# 1power.net
KiCad netlist of a schematic drawn in Altium Designer
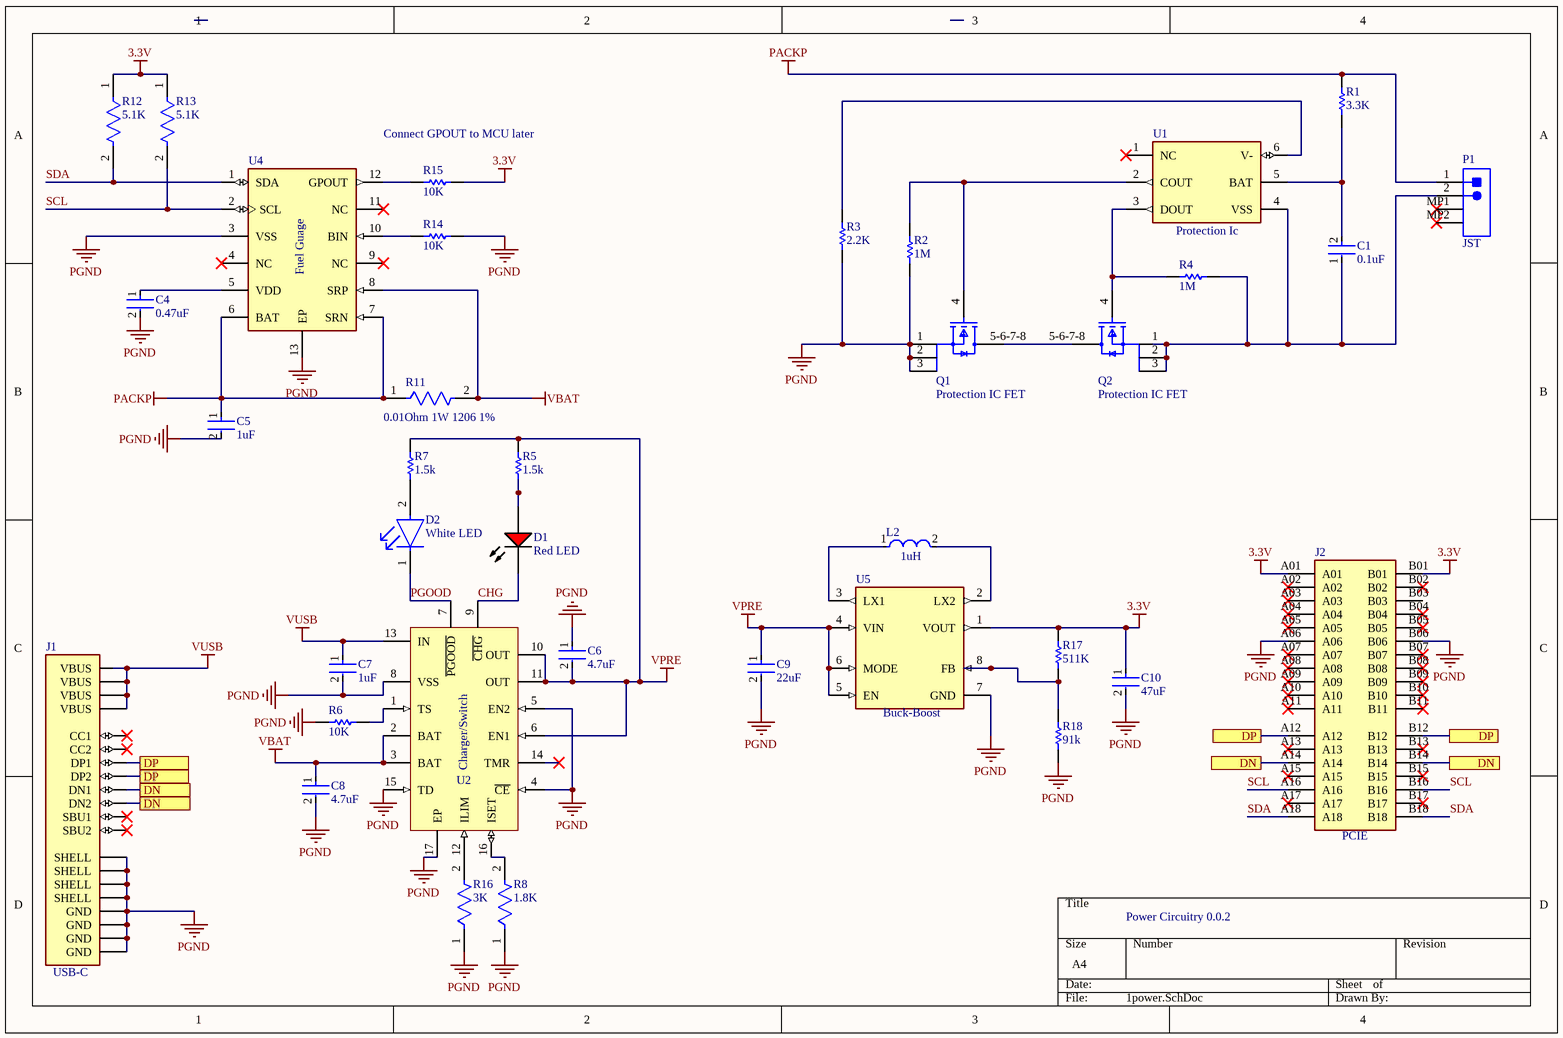
[diagram p0: 1power.SchDoc]

(export (version "E")
  (design (tool "Eeschema 10.0.6"))
  (components
    (comp (ref "C1")
      (value "0.1uF")
      (footprint "FP-GRM15-MFG")
      (description "CAP CER 0.1UF 16V X7R 0402")
      (fields (field (name "MANUFACTURER PART NUMBER") "GRM155R71C104KA88D") (field (name "TOLERANCE") "10%"))
      (libsource (lib "Altium Content Vault") (part "236180d848d6139a670b325ea6854c9"))
    )
    (comp (ref "C4")
      (value "0.47uF")
      (footprint "FP-C0603C-CF-MFG")
      (description "CAP CER 0.47UF 16V X7R 0603")
      (fields (field (name "TOLERANCE") "0.1") (field (name "MANUFACTURER PART NUMBER") "C0603C474K4RACTU"))
      (libsource (lib "Altium Content Vault") (part "b4654b650e69147ec39a6b967a45e02"))
    )
    (comp (ref "C5")
      (value "1uF")
      (footprint "FP-C0402C105K8PACTU-MFG")
      (description "CAP CER 1UF 10V X5R 0402")
      (fields (field (name "VOLTAGE") "10V") (field (name "TOLERANCE") "10%"))
      (libsource (lib "Altium Content Vault") (part "11868f565c42a9108669ba33697ecf6"))
    )
    (comp (ref "C6")
      (value "4.7uF")
      (footprint "FP-ZRB15X-0_15-MFG")
      (description "CAP CER 4.7UF 10V X5R 0402")
      (fields (field (name "TOLERANCE") "20%") (field (name "VOLTAGE") "10V"))
      (libsource (lib "Altium Content Vault") (part "b4654b650e69147ec39a6b967a45e02"))
    )
    (comp (ref "C7")
      (value "1uF")
      (footprint "FP-C0402C105K8PACTU-MFG")
      (description "CAP CER 1UF 10V X5R 0402")
      (fields (field (name "VOLTAGE") "10V") (field (name "TOLERANCE") "10%"))
      (libsource (lib "Altium Content Vault") (part "11868f565c42a9108669ba33697ecf6"))
    )
    (comp (ref "C8")
      (value "4.7uF")
      (footprint "FP-ZRB15X-0_15-MFG")
      (description "CAP CER 4.7UF 10V X5R 0402")
      (fields (field (name "TOLERANCE") "20%") (field (name "VOLTAGE") "10V"))
      (libsource (lib "Altium Content Vault") (part "b4654b650e69147ec39a6b967a45e02"))
    )
    (comp (ref "C9")
      (value "22uF")
      (footprint "FP-GRM187-0_2-IPC_C")
      (description "Chip Multilayer Ceramic Capacitors for General Purpose, 0603, 22uF, X5R, 15%, 20%, 10V")
      (fields (field (name "TOLERANCE") "20%"))
      (libsource (lib "Altium Content Vault") (part "02cd4be3c70576c341d710602a673aa"))
    )
    (comp (ref "C10")
      (value "47uF")
      (footprint "FP-GRM219-0_2-0_1-IPC_A")
      (description "Chip Multilayer Ceramic Capacitors for General Purpose, 0805, 47uF, X5R, 15%, 20%, 6.3V")
      (fields (field (name "TOLERANCE") "20%"))
      (libsource (lib "Altium Content Vault") (part "02cd4be3c70576c341d710602a673aa"))
    )
    (comp (ref "D1")
      (value "Red LED")
      (footprint "VISH-TLMS1000_V")
      (description "Low Current LED, 40 mW, 1.8 V, -40 to 100 degC, 2-Pin SMD (0603), RoHS, Tape and Reel")
      (fields (field (name "MANUFACTURER") "Vishay"))
      (libsource (lib "Altium Content Vault") (part "LED-RED-AK-2"))
    )
    (comp (ref "D2")
      (value "White LED")
      (footprint "FP-6_541-5091_01-4-MFG")
      (description "LED COOL WHITE 0603 SMD")
      (fields
        (field (name "MANUFACTURER") "Vishay")
        (field (name "MANUFACTURER PART NUMBER") "VLMW1300-GS08")
      )
      (libsource (lib "Altium Content Vault") (part "8706943c75ba83719d021d2fdc84c58"))
    )
    (comp (ref "J1")
      (value "USB-C")
      (footprint "GCT_USB4085-GF-A_REVB")
      (fields (field (name "MF") "Global Connector Technology") (field (name "MP") "USB4085-GF-A"))
      (libsource (lib "Schlib1") (part "USB4085-GF-A_REVB"))
    )
    (comp (ref "J2")
      (value "PCIE")
      (footprint "SAMTEC_PCIE-036-02-X-D-EMS3")
      (description "PCI EXPRESS EDGE MOUNT ASSEMBLY,36PINS.")
      (fields (field (name "MP") "PCIE-036-02-X-D-EMS3"))
      (libsource (lib "Schlib1") (part "PCIE-036-02-X-D-EMS3"))
    )
    (comp (ref "L2")
      (value "1uH")
      (footprint "FP-DFE252012C-IPC_B")
      (description "Shielded Wirewound Inductor 1uH 20% 3200mA 0.042Ω 1008 (2520), DFE252012P-1R0M=P2")
      (fields (field (name "TOLERANCE") "20%"))
      (libsource (lib "Altium Content Vault") (part "725321dda6339637d4d059423bc1c3c"))
    )
    (comp (ref "P1")
      (value "JST")
      (footprint "JST- S2B-PH-SM4-TB(LF)(SN)-2_V")
      (description "Male Header, Pitch 2 mm, 1 x 2 Position, Height 5.5 mm, -25 to 85 degC, RoHS, Tape and Reel")
      (libsource (lib "Schlib1") (part "CMP-1755-00001-1"))
    )
    (comp (ref "Q1")
      (value "Protection IC FET")
      (footprint "FP-DQG0008A-MFG")
      (description "Protection IC FET, MOSFET N-CH 25V 60A 8-SON, CSD16406Q3")
      (libsource (lib "Schlib1") (part "CMP-04962-000044-1"))
    )
    (comp (ref "Q2")
      (value "Protection IC FET")
      (footprint "FP-DQG0008A-MFG")
      (description "Protection IC FET, MOSFET N-CH 25V 60A 8-SON, CSD16406Q3")
      (libsource (lib "Schlib1") (part "CMP-04962-000044-1"))
    )
    (comp (ref "R1")
      (value "3.3K")
      (footprint "RESC1005X40X25LL05T10")
      (fields (field (name "MANUFACTURER") "Yageo / Phycomp") (field (name "PART NUMBER") "RC0402FR-073K3L"))
      (libsource (lib "Altium Content Vault") (part "RES"))
    )
    (comp (ref "R2")
      (value "1M")
      (footprint "RESC1005X40X25NL05T10")
      (fields (field (name "MANUFACTURER") "Yageo / Phycomp") (field (name "PART NUMBER") "RC0402FR-071ML"))
      (libsource (lib "Altium Content Vault") (part "RES"))
    )
    (comp (ref "R3")
      (value "2.2K")
      (footprint "RESC1005X40X25NL05T10")
      (fields (field (name "MANUFACTURER") "Yageo / Phycomp") (field (name "PART NUMBER") "RC0402FR-072K2L"))
      (libsource (lib "Altium Content Vault") (part "RES"))
    )
    (comp (ref "R4")
      (value "1M")
      (footprint "RESC1005X40X25NL05T10")
      (fields (field (name "MANUFACTURER") "Yageo / Phycomp") (field (name "PART NUMBER") "RC0402FR-071ML"))
      (libsource (lib "Altium Content Vault") (part "RES"))
    )
    (comp (ref "R5")
      (value "1.5k")
      (footprint "RESC1005X40X25ML05T10")
      (fields (field (name "MANUFACTURER") "Yageo / Phycomp") (field (name "PART NUMBER") "RC0402FR-071K5L"))
      (libsource (lib "Altium Content Vault") (part "RES"))
    )
    (comp (ref "R6")
      (value "10K")
      (footprint "RESC1005X40X25LL05T10")
      (fields (field (name "PART NUMBER") "RC0402FR-0710KL") (field (name "MANUFACTURER") "Yageo / Phycomp"))
      (libsource (lib "Altium Content Vault") (part "RES"))
    )
    (comp (ref "R7")
      (value "1.5k")
      (footprint "RESC1005X40X25ML05T10")
      (fields (field (name "MANUFACTURER") "Yageo / Phycomp") (field (name "PART NUMBER") "RC0402FR-071K5L"))
      (libsource (lib "Altium Content Vault") (part "RES"))
    )
    (comp (ref "R8")
      (value "1.8K")
      (footprint "FP-CRCW0603-e3-IPC_A")
      (description "RES Thick Film, 1.8kΩ, 1%, 0.1W, 100ppm/°C, 0603")
      (fields (field (name "TOLERANCE") "1%"))
      (libsource (lib "Altium Content Vault") (part "1029c3af85768c4190bb7ad29bc67b5"))
    )
    (comp (ref "R11")
      (value "0.01Ohm 1W 1206 1%")
      (footprint "FP-WSLP1206-FP_1_65x1_93x-MFG")
      (description "RES 0.01 OHM 1% 1W 1206")
      (fields (field (name "TOLERANCE") "1%"))
      (libsource (lib "Altium Content Vault") (part "1029c3af85768c4190bb7ad29bc67b5"))
    )
    (comp (ref "R12")
      (value "5.1K")
      (footprint "FP-CRCW0402-e3-IPC_A")
      (description "RES Thick Film, 5.1kΩ, 1%, 0.063W, 100ppm/°C, 0402")
      (fields (field (name "TOLERANCE") "1%"))
      (libsource (lib "Altium Content Vault") (part "1029c3af85768c4190bb7ad29bc67b5"))
    )
    (comp (ref "R13")
      (value "5.1K")
      (footprint "FP-CRCW0402-e3-IPC_A")
      (description "RES Thick Film, 5.1kΩ, 1%, 0.063W, 100ppm/°C, 0402")
      (fields (field (name "TOLERANCE") "1%"))
      (libsource (lib "Altium Content Vault") (part "1029c3af85768c4190bb7ad29bc67b5"))
    )
    (comp (ref "R14")
      (value "10K")
      (footprint "RESC1005X40X25LL05T10")
      (fields (field (name "PART NUMBER") "RC0402FR-0710KL") (field (name "MANUFACTURER") "Yageo / Phycomp"))
      (libsource (lib "Altium Content Vault") (part "RES"))
    )
    (comp (ref "R15")
      (value "10K")
      (footprint "RESC1005X40X25LL05T10")
      (fields (field (name "PART NUMBER") "RC0402FR-0710KL") (field (name "MANUFACTURER") "Yageo / Phycomp"))
      (libsource (lib "Altium Content Vault") (part "RES"))
    )
    (comp (ref "R16")
      (value "3K")
      (footprint "FP-CRCW0603-e3-MFG")
      (description "RES Thick Film, 3kΩ, 1%, 0.1W, 100ppm/°C, 0603")
      (fields (field (name "TOLERANCE") "1%"))
      (libsource (lib "Altium Content Vault") (part "1029c3af85768c4190bb7ad29bc67b5"))
    )
    (comp (ref "R17")
      (value "511K")
      (footprint "RESC1005X40X25ML05T05")
      (fields (field (name "PART NUMBER") "ERJ-2RKF5113X") (field (name "MANUFACTURER") "Panasonic"))
      (libsource (lib "Altium Content Vault") (part "RES"))
    )
    (comp (ref "R18")
      (value "91k")
      (footprint "RESC1005X40X25NL05T10")
      (fields (field (name "MANUFACTURER") "Yageo / Phycomp") (field (name "PART NUMBER") "RC0402FR-0791KL"))
      (libsource (lib "Altium Content Vault") (part "RES"))
    )
    (comp (ref "U1")
      (value "Protection Ic")
      (footprint "FP-DSE0006A-IPC_A")
      (description "Power Supply Support Circuit, Fixed, 1 Channel, PDSO6")
      (fields
        (field (name "MANUFACTURER") "Texas Instruments")
        (field (name "MANUFACTURER PART NUMBER") "BQ29701DSER")
      )
      (libsource (lib "Schlib1") (part "BQ29701DSER"))
    )
    (comp (ref "U2")
      (value "Charger/Switch")
      (footprint "RGT0016C_V")
      (fields (field (name "PARTNUMBER") "BQ24072RGTT") (field (name "MANUFACTURER") "Texas Instruments"))
      (libsource (lib "Altium Content Vault") (part "TI-BQ24072RGT16-1700X1700TP"))
    )
    (comp (ref "U4")
      (value "Fuel Guage")
      (footprint "FP-DRZ0012A-MFG")
      (description "IC BATT FUEL GAUGE LICOO2 12SON")
      (fields
        (field (name "OCTOPART") "https://octopart.com/bq27441drzt-g1a-texas+instruments-30555831")
        (field (name "MANUFACTURER") "Texas Instruments")
      )
      (libsource (lib "Altium Content Vault") (part "c803e035ce0891ae19034f27297cdee"))
    )
    (comp (ref "U5")
      (value "Buck-Boost")
      (footprint "SOT50P160X60-8N")
      (description "1.5-A output current, high-power-density buck-boost converter")
      (fields (field (name "MF") "Texas Instruments") (field (name "MP") "TPS631000DRLR"))
      (libsource (lib "Schlib1") (part "TPS631000DRLR"))
    )
  )
  (nets
    (net (code "1") (name "/CHG") (class "Default")
      (node (ref "D1") (pin "2") (pinfunction "K_2") (pintype "passive"))
      (node (ref "U2") (pin "9") (pinfunction "~{CHG}_9") (pintype "tri_state"))
    )
    (net (code "2") (name "/DN") (class "Default")
      (node (ref "J1") (pin "A7") (pinfunction "DN1_A7") (pintype "bidirectional"))
      (node (ref "J1") (pin "B7") (pinfunction "DN2_B7") (pintype "bidirectional"))
      (node (ref "J2") (pin "A14") (pinfunction "A14_A14") (pintype "passive"))
      (node (ref "J2") (pin "B14") (pinfunction "B14_B14") (pintype "passive"))
    )
    (net (code "3") (name "/DP") (class "Default")
      (node (ref "J1") (pin "A6") (pinfunction "DP1_A6") (pintype "bidirectional"))
      (node (ref "J1") (pin "B6") (pinfunction "DP2_B6") (pintype "bidirectional"))
      (node (ref "J2") (pin "A12") (pinfunction "A12_A12") (pintype "passive"))
      (node (ref "J2") (pin "B12") (pinfunction "B12_B12") (pintype "passive"))
    )
    (net (code "4") (name "/PGOOD") (class "Default")
      (node (ref "D2") (pin "1") (pinfunction "C_1") (pintype "passive"))
      (node (ref "U2") (pin "7") (pinfunction "~{PGOOD}_7") (pintype "tri_state"))
    )
    (net (code "5") (name "/SCL") (class "Default")
      (node (ref "J2") (pin "A16") (pinfunction "A16_A16") (pintype "passive"))
      (node (ref "J2") (pin "B16") (pinfunction "B16_B16") (pintype "passive"))
      (node (ref "R13") (pin "2") (pinfunction "2_2") (pintype "passive"))
      (node (ref "U4") (pin "2") (pinfunction "SCL_2") (pintype "bidirectional"))
    )
    (net (code "6") (name "/SDA") (class "Default")
      (node (ref "J2") (pin "A18") (pinfunction "A18_A18") (pintype "passive"))
      (node (ref "J2") (pin "B18") (pinfunction "B18_B18") (pintype "passive"))
      (node (ref "R12") (pin "2") (pinfunction "2_2") (pintype "passive"))
      (node (ref "U4") (pin "1") (pinfunction "SDA_1") (pintype "bidirectional"))
    )
    (net (code "7") (name "3.3V") (class "Default")
      (node (ref "C10") (pin "1") (pinfunction "1_1") (pintype "passive"))
      (node (ref "J2") (pin "A01") (pinfunction "A01_A01") (pintype "passive"))
      (node (ref "J2") (pin "B01") (pinfunction "B01_B01") (pintype "passive"))
      (node (ref "R12") (pin "1") (pinfunction "1_1") (pintype "passive"))
      (node (ref "R13") (pin "1") (pinfunction "1_1") (pintype "passive"))
      (node (ref "R15") (pin "2") (pinfunction "2_2") (pintype "passive"))
      (node (ref "R17") (pin "2") (pinfunction "2_2") (pintype "passive"))
      (node (ref "U5") (pin "1") (pinfunction "VOUT_1") (pintype "output"))
    )
    (net (code "8") (name "Net-(D1-A)") (class "Default")
      (node (ref "D1") (pin "1") (pinfunction "A_1") (pintype "passive"))
      (node (ref "R5") (pin "1") (pinfunction "1_1") (pintype "passive"))
    )
    (net (code "9") (name "Net-(D2-A)") (class "Default")
      (node (ref "D2") (pin "2") (pinfunction "A_2") (pintype "passive"))
      (node (ref "R7") (pin "1") (pinfunction "1_1") (pintype "passive"))
    )
    (net (code "10") (name "Net-(Q1-D)") (class "Default")
      (node (ref "Q1") (pin "5-6-7-8") (pinfunction "D_5-6-7-8") (pintype "passive"))
      (node (ref "Q2") (pin "5-6-7-8") (pinfunction "D_5-6-7-8") (pintype "passive"))
    )
    (net (code "11") (name "Net-(Q1-G)") (class "Default")
      (node (ref "Q1") (pin "4") (pinfunction "G_4") (pintype "passive"))
      (node (ref "R2") (pin "2") (pinfunction "2_2") (pintype "passive"))
      (node (ref "U1") (pin "2") (pinfunction "COUT_2") (pintype "output"))
    )
    (net (code "12") (name "Net-(Q2-G)") (class "Default")
      (node (ref "Q2") (pin "4") (pinfunction "G_4") (pintype "passive"))
      (node (ref "R4") (pin "1") (pinfunction "1_1") (pintype "passive"))
      (node (ref "U1") (pin "3") (pinfunction "DOUT_3") (pintype "output"))
    )
    (net (code "13") (name "Net-(U1-BAT)") (class "Default")
      (node (ref "C1") (pin "2") (pinfunction "2_2") (pintype "passive"))
      (node (ref "R1") (pin "2") (pinfunction "2_2") (pintype "passive"))
      (node (ref "U1") (pin "5") (pinfunction "BAT_5") (pintype "power_in"))
    )
    (net (code "14") (name "Net-(U1-V-)") (class "Default")
      (node (ref "R3") (pin "2") (pinfunction "2_2") (pintype "passive"))
      (node (ref "U1") (pin "6") (pinfunction "V-_6") (pintype "bidirectional"))
    )
    (net (code "15") (name "Net-(U1-VSS)") (class "Default")
      (node (ref "C1") (pin "1") (pinfunction "1_1") (pintype "passive"))
      (node (ref "P1") (pin "2") (pinfunction "2_2") (pintype "passive"))
      (node (ref "Q2") (pin "1") (pinfunction "S_1") (pintype "passive"))
      (node (ref "Q2") (pin "2") (pinfunction "S_2") (pintype "passive"))
      (node (ref "Q2") (pin "3") (pinfunction "S_3") (pintype "passive"))
      (node (ref "R4") (pin "2") (pinfunction "2_2") (pintype "passive"))
      (node (ref "U1") (pin "4") (pinfunction "VSS_4") (pintype "power_in"))
    )
    (net (code "16") (name "Net-(U2-ILIM)") (class "Default")
      (node (ref "R16") (pin "2") (pinfunction "2_2") (pintype "passive"))
      (node (ref "U2") (pin "12") (pinfunction "ILIM_12") (pintype "input"))
    )
    (net (code "17") (name "Net-(U2-ISET)") (class "Default")
      (node (ref "R8") (pin "2") (pinfunction "2_2") (pintype "passive"))
      (node (ref "U2") (pin "16") (pinfunction "ISET_16") (pintype "bidirectional"))
    )
    (net (code "18") (name "Net-(U2-TS)") (class "Default")
      (node (ref "R6") (pin "2") (pinfunction "2_2") (pintype "passive"))
      (node (ref "U2") (pin "1") (pinfunction "TS_1") (pintype "input"))
    )
    (net (code "19") (name "Net-(U4-BIN)") (class "Default")
      (node (ref "R14") (pin "1") (pinfunction "1_1") (pintype "passive"))
      (node (ref "U4") (pin "10") (pinfunction "BIN_10") (pintype "input"))
    )
    (net (code "20") (name "Net-(U4-GPOUT)") (class "Default")
      (node (ref "R15") (pin "1") (pinfunction "1_1") (pintype "passive"))
      (node (ref "U4") (pin "12") (pinfunction "GPOUT_12") (pintype "output"))
    )
    (net (code "21") (name "Net-(U4-VDD)") (class "Default")
      (node (ref "C4") (pin "1") (pinfunction "1_1") (pintype "passive"))
      (node (ref "U4") (pin "5") (pinfunction "VDD_5") (pintype "power_in"))
    )
    (net (code "22") (name "Net-(U5-FB)") (class "Default")
      (node (ref "R17") (pin "1") (pinfunction "1_1") (pintype "passive"))
      (node (ref "R18") (pin "2") (pinfunction "2_2") (pintype "passive"))
      (node (ref "U5") (pin "8") (pinfunction "FB_8") (pintype "input"))
    )
    (net (code "23") (name "Net-(U5-LX1)") (class "Default")
      (node (ref "L2") (pin "1") (pinfunction "1_1") (pintype "passive"))
      (node (ref "U5") (pin "3") (pinfunction "LX1_3") (pintype "output"))
    )
    (net (code "24") (name "Net-(U5-LX2)") (class "Default")
      (node (ref "L2") (pin "2") (pinfunction "2_2") (pintype "passive"))
      (node (ref "U5") (pin "2") (pinfunction "LX2_2") (pintype "output"))
    )
    (net (code "25") (name "PACKP") (class "Default")
      (node (ref "C5") (pin "1") (pinfunction "1_1") (pintype "passive"))
      (node (ref "P1") (pin "1") (pinfunction "1_1") (pintype "passive"))
      (node (ref "R1") (pin "1") (pinfunction "1_1") (pintype "passive"))
      (node (ref "R11") (pin "1") (pinfunction "1_1") (pintype "passive"))
      (node (ref "U4") (pin "6") (pinfunction "BAT_6") (pintype "power_in"))
      (node (ref "U4") (pin "7") (pinfunction "SRN_7") (pintype "input"))
    )
    (net (code "26") (name "PGND") (class "Default")
      (node (ref "C10") (pin "2") (pinfunction "2_2") (pintype "passive"))
      (node (ref "C4") (pin "2") (pinfunction "2_2") (pintype "passive"))
      (node (ref "C5") (pin "2") (pinfunction "2_2") (pintype "passive"))
      (node (ref "C6") (pin "1") (pinfunction "1_1") (pintype "passive"))
      (node (ref "C7") (pin "2") (pinfunction "2_2") (pintype "passive"))
      (node (ref "C8") (pin "2") (pinfunction "2_2") (pintype "passive"))
      (node (ref "C9") (pin "2") (pinfunction "2_2") (pintype "passive"))
      (node (ref "J1") (pin "A1") (pinfunction "GND_A1") (pintype "power_in"))
      (node (ref "J1") (pin "A12") (pinfunction "GND_A12") (pintype "power_in"))
      (node (ref "J1") (pin "B1") (pinfunction "GND_B1") (pintype "power_in"))
      (node (ref "J1") (pin "B12") (pinfunction "GND_B12") (pintype "power_in"))
      (node (ref "J1") (pin "S1") (pinfunction "SHELL_S1") (pintype "passive"))
      (node (ref "J1") (pin "S2") (pinfunction "SHELL_S2") (pintype "passive"))
      (node (ref "J1") (pin "S3") (pinfunction "SHELL_S3") (pintype "passive"))
      (node (ref "J1") (pin "S4") (pinfunction "SHELL_S4") (pintype "passive"))
      (node (ref "J2") (pin "A06") (pinfunction "A06_A06") (pintype "passive"))
      (node (ref "J2") (pin "B06") (pinfunction "B06_B06") (pintype "passive"))
      (node (ref "Q1") (pin "1") (pinfunction "S_1") (pintype "passive"))
      (node (ref "Q1") (pin "2") (pinfunction "S_2") (pintype "passive"))
      (node (ref "Q1") (pin "3") (pinfunction "S_3") (pintype "passive"))
      (node (ref "R14") (pin "2") (pinfunction "2_2") (pintype "passive"))
      (node (ref "R16") (pin "1") (pinfunction "1_1") (pintype "passive"))
      (node (ref "R18") (pin "1") (pinfunction "1_1") (pintype "passive"))
      (node (ref "R2") (pin "1") (pinfunction "1_1") (pintype "passive"))
      (node (ref "R3") (pin "1") (pinfunction "1_1") (pintype "passive"))
      (node (ref "R6") (pin "1") (pinfunction "1_1") (pintype "passive"))
      (node (ref "R8") (pin "1") (pinfunction "1_1") (pintype "passive"))
      (node (ref "U2") (pin "15") (pinfunction "TD_15") (pintype "input"))
      (node (ref "U2") (pin "17") (pinfunction "EP_17") (pintype "power_in"))
      (node (ref "U2") (pin "4") (pinfunction "~{CE}_4") (pintype "input"))
      (node (ref "U2") (pin "5") (pinfunction "EN2_5") (pintype "input"))
      (node (ref "U2") (pin "8") (pinfunction "VSS_8") (pintype "power_in"))
      (node (ref "U4") (pin "13") (pinfunction "EP_13") (pintype "power_in"))
      (node (ref "U4") (pin "3") (pinfunction "VSS_3") (pintype "power_in"))
      (node (ref "U5") (pin "7") (pinfunction "GND_7") (pintype "power_in"))
    )
    (net (code "27") (name "VBAT") (class "Default")
      (node (ref "C8") (pin "1") (pinfunction "1_1") (pintype "passive"))
      (node (ref "R11") (pin "2") (pinfunction "2_2") (pintype "passive"))
      (node (ref "U2") (pin "2") (pinfunction "BAT_2") (pintype "power_in"))
      (node (ref "U2") (pin "3") (pinfunction "BAT_3") (pintype "power_in"))
      (node (ref "U4") (pin "8") (pinfunction "SRP_8") (pintype "input"))
    )
    (net (code "28") (name "VPRE") (class "Default")
      (node (ref "C6") (pin "2") (pinfunction "2_2") (pintype "passive"))
      (node (ref "C9") (pin "1") (pinfunction "1_1") (pintype "passive"))
      (node (ref "R5") (pin "2") (pinfunction "2_2") (pintype "passive"))
      (node (ref "R7") (pin "2") (pinfunction "2_2") (pintype "passive"))
      (node (ref "U2") (pin "10") (pinfunction "OUT_10") (pintype "power_in"))
      (node (ref "U2") (pin "11") (pinfunction "OUT_11") (pintype "power_in"))
      (node (ref "U2") (pin "6") (pinfunction "EN1_6") (pintype "input"))
      (node (ref "U5") (pin "4") (pinfunction "VIN_4") (pintype "input"))
      (node (ref "U5") (pin "5") (pinfunction "EN_5") (pintype "input"))
      (node (ref "U5") (pin "6") (pinfunction "MODE_6") (pintype "input"))
    )
    (net (code "29") (name "VUSB") (class "Default")
      (node (ref "C7") (pin "1") (pinfunction "1_1") (pintype "passive"))
      (node (ref "J1") (pin "A4") (pinfunction "VBUS_A4") (pintype "power_in"))
      (node (ref "J1") (pin "A9") (pinfunction "VBUS_A9") (pintype "power_in"))
      (node (ref "J1") (pin "B4") (pinfunction "VBUS_B4") (pintype "power_in"))
      (node (ref "J1") (pin "B9") (pinfunction "VBUS_B9") (pintype "power_in"))
      (node (ref "U2") (pin "13") (pinfunction "IN_13") (pintype "power_in"))
    )
    (net (code "30") (name "unconnected-(J1-CC1-PadA5)") (class "Default")
      (node (ref "J1") (pin "A5") (pinfunction "CC1_A5") (pintype "bidirectional+no_connect"))
    )
    (net (code "31") (name "unconnected-(J1-CC2-PadB5)") (class "Default")
      (node (ref "J1") (pin "B5") (pinfunction "CC2_B5") (pintype "bidirectional+no_connect"))
    )
    (net (code "32") (name "unconnected-(J1-SBU1-PadA8)") (class "Default")
      (node (ref "J1") (pin "A8") (pinfunction "SBU1_A8") (pintype "bidirectional+no_connect"))
    )
    (net (code "33") (name "unconnected-(J1-SBU2-PadB8)") (class "Default")
      (node (ref "J1") (pin "B8") (pinfunction "SBU2_B8") (pintype "bidirectional+no_connect"))
    )
    (net (code "34") (name "unconnected-(J2-PadA02)") (class "Default")
      (node (ref "J2") (pin "A02") (pinfunction "A02_A02") (pintype "passive+no_connect"))
    )
    (net (code "35") (name "unconnected-(J2-PadA03)") (class "Default")
      (node (ref "J2") (pin "A03") (pinfunction "A03_A03") (pintype "passive+no_connect"))
    )
    (net (code "36") (name "unconnected-(J2-PadA04)") (class "Default")
      (node (ref "J2") (pin "A04") (pinfunction "A04_A04") (pintype "passive+no_connect"))
    )
    (net (code "37") (name "unconnected-(J2-PadA05)") (class "Default")
      (node (ref "J2") (pin "A05") (pinfunction "A05_A05") (pintype "passive+no_connect"))
    )
    (net (code "38") (name "unconnected-(J2-PadA07)") (class "Default")
      (node (ref "J2") (pin "A07") (pinfunction "A07_A07") (pintype "passive+no_connect"))
    )
    (net (code "39") (name "unconnected-(J2-PadA08)") (class "Default")
      (node (ref "J2") (pin "A08") (pinfunction "A08_A08") (pintype "passive+no_connect"))
    )
    (net (code "40") (name "unconnected-(J2-PadA09)") (class "Default")
      (node (ref "J2") (pin "A09") (pinfunction "A09_A09") (pintype "passive+no_connect"))
    )
    (net (code "41") (name "unconnected-(J2-PadA10)") (class "Default")
      (node (ref "J2") (pin "A10") (pinfunction "A10_A10") (pintype "passive+no_connect"))
    )
    (net (code "42") (name "unconnected-(J2-PadA11)") (class "Default")
      (node (ref "J2") (pin "A11") (pinfunction "A11_A11") (pintype "passive+no_connect"))
    )
    (net (code "43") (name "unconnected-(J2-PadA13)") (class "Default")
      (node (ref "J2") (pin "A13") (pinfunction "A13_A13") (pintype "passive+no_connect"))
    )
    (net (code "44") (name "unconnected-(J2-PadA15)") (class "Default")
      (node (ref "J2") (pin "A15") (pinfunction "A15_A15") (pintype "passive+no_connect"))
    )
    (net (code "45") (name "unconnected-(J2-PadA17)") (class "Default")
      (node (ref "J2") (pin "A17") (pinfunction "A17_A17") (pintype "passive+no_connect"))
    )
    (net (code "46") (name "unconnected-(J2-PadB02)") (class "Default")
      (node (ref "J2") (pin "B02") (pinfunction "B02_B02") (pintype "passive+no_connect"))
    )
    (net (code "47") (name "unconnected-(J2-PadB03)") (class "Default")
      (node (ref "J2") (pin "B03") (pinfunction "B03_B03") (pintype "passive"))
    )
    (net (code "48") (name "unconnected-(J2-PadB04)") (class "Default")
      (node (ref "J2") (pin "B04") (pinfunction "B04_B04") (pintype "passive+no_connect"))
    )
    (net (code "49") (name "unconnected-(J2-PadB05)") (class "Default")
      (node (ref "J2") (pin "B05") (pinfunction "B05_B05") (pintype "passive+no_connect"))
    )
    (net (code "50") (name "unconnected-(J2-PadB07)") (class "Default")
      (node (ref "J2") (pin "B07") (pinfunction "B07_B07") (pintype "passive+no_connect"))
    )
    (net (code "51") (name "unconnected-(J2-PadB08)") (class "Default")
      (node (ref "J2") (pin "B08") (pinfunction "B08_B08") (pintype "passive+no_connect"))
    )
    (net (code "52") (name "unconnected-(J2-PadB09)") (class "Default")
      (node (ref "J2") (pin "B09") (pinfunction "B09_B09") (pintype "passive+no_connect"))
    )
    (net (code "53") (name "unconnected-(J2-PadB10)") (class "Default")
      (node (ref "J2") (pin "B10") (pinfunction "B10_B10") (pintype "passive+no_connect"))
    )
    (net (code "54") (name "unconnected-(J2-PadB11)") (class "Default")
      (node (ref "J2") (pin "B11") (pinfunction "B11_B11") (pintype "passive+no_connect"))
    )
    (net (code "55") (name "unconnected-(J2-PadB13)") (class "Default")
      (node (ref "J2") (pin "B13") (pinfunction "B13_B13") (pintype "passive+no_connect"))
    )
    (net (code "56") (name "unconnected-(J2-PadB15)") (class "Default")
      (node (ref "J2") (pin "B15") (pinfunction "B15_B15") (pintype "passive+no_connect"))
    )
    (net (code "57") (name "unconnected-(J2-PadB17)") (class "Default")
      (node (ref "J2") (pin "B17") (pinfunction "B17_B17") (pintype "passive+no_connect"))
    )
    (net (code "58") (name "unconnected-(P1-PadMP1)") (class "Default")
      (node (ref "P1") (pin "MP1") (pinfunction "MP1_MP1") (pintype "passive+no_connect"))
    )
    (net (code "59") (name "unconnected-(P1-PadMP2)") (class "Default")
      (node (ref "P1") (pin "MP2") (pinfunction "MP2_MP2") (pintype "passive+no_connect"))
    )
    (net (code "60") (name "unconnected-(U1-NC-Pad1)") (class "Default")
      (node (ref "U1") (pin "1") (pinfunction "NC_1") (pintype "passive+no_connect"))
    )
    (net (code "61") (name "unconnected-(U2-TMR-Pad14)") (class "Default")
      (node (ref "U2") (pin "14") (pinfunction "TMR_14") (pintype "passive+no_connect"))
    )
    (net (code "62") (name "unconnected-(U4-NC-Pad4)") (class "Default")
      (node (ref "U4") (pin "4") (pinfunction "NC_4") (pintype "passive+no_connect"))
    )
    (net (code "63") (name "unconnected-(U4-NC-Pad9)") (class "Default")
      (node (ref "U4") (pin "9") (pinfunction "NC_9") (pintype "power_in+no_connect"))
    )
    (net (code "64") (name "unconnected-(U4-NC-Pad11)") (class "Default")
      (node (ref "U4") (pin "11") (pinfunction "NC_11") (pintype "passive+no_connect"))
    )
  )
)
